# PWR_RELAY.net
KiCad netlist of a schematic drawn in Altium Designer
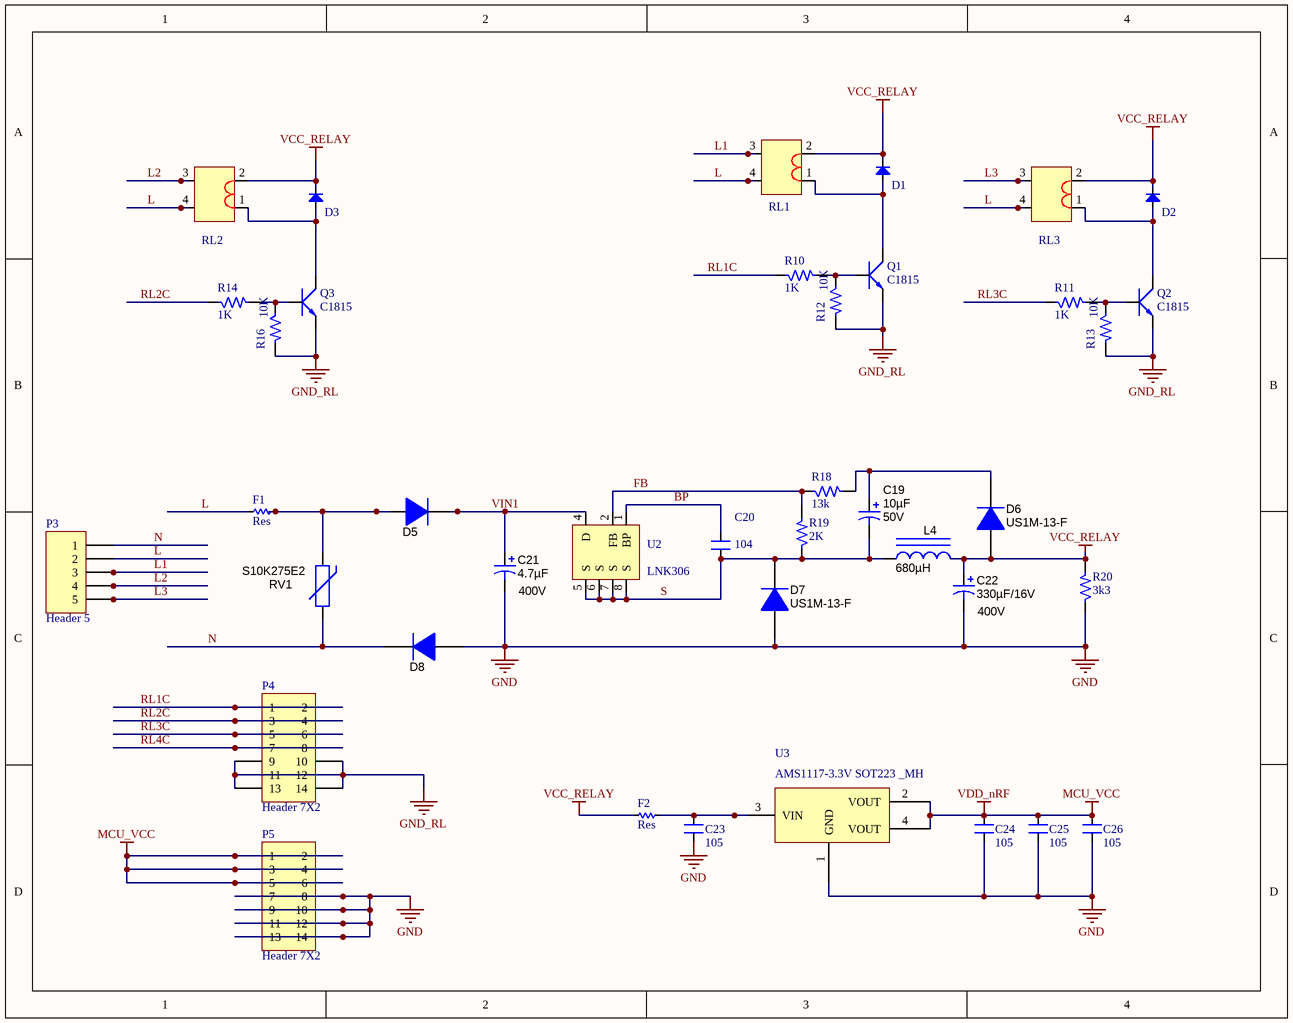
[diagram p0: PWR&RELAY.SchDoc]

(export (version "E")
  (design (tool "Eeschema 10.0.6"))
  (components
    (comp (ref "C19")
      (value "ECA-1HHG100")
      (footprint "PcbLib1:NHG_500x1100")
      (description "CAP, AL, 10 µF, 50 V, +/- 20%, TH")
      (fields
        (field (name "VALUEDISPLAYED") "10µF")
        (field (name "MANUFACTURER") "Panasonic")
        (field (name "VALUE2") "50V")
        (field (name "PUBLISHER") "Texas Instruments")
      )
      (libsource (lib "Capacitor_Aluminum") (part "ECA-1HHG100"))
    )
    (comp (ref "C20")
      (value "104")
      (footprint "0805_HV")
      (description "Cap SMD")
      (libsource (lib "hatcatbietbay") (part "CM"))
    )
    (comp (ref "C21")
      (value "400AX6R8M8x11")
      (footprint "PcbLib1:PANACAP-G-GENERIC")
      (description "CAP, AL, 6.8uF, 400V, +/-20%, TH")
      (fields
        (field (name "VALUEDISPLAYED") "4.7µF")
        (field (name "MANUFACTURER") "Rubycon")
        (field (name "VALUE2") "400V")
        (field (name "PUBLISHER") "Texas Instruments")
      )
      (libsource (lib "Capacitor_Aluminum") (part "400AX6R8M8x11"))
    )
    (comp (ref "C22")
      (value "400AX6R8M8x11")
      (footprint "PcbLib1:CAPPRD350W60D800H1100")
      (description "CAP, AL, 6.8uF, 400V, +/-20%, TH")
      (fields
        (field (name "VALUEDISPLAYED") "330µF/16V")
        (field (name "MANUFACTURER") "Rubycon")
        (field (name "VALUE2") "400V")
        (field (name "PUBLISHER") "Texas Instruments")
      )
      (libsource (lib "Capacitor_Aluminum") (part "400AX6R8M8x11"))
    )
    (comp (ref "C23")
      (value "105")
      (footprint "0805_HV")
      (description "Cap SMD")
      (libsource (lib "hatcatbietbay") (part "CM"))
    )
    (comp (ref "C24")
      (value "105")
      (footprint "0805_HV")
      (description "Cap SMD")
      (libsource (lib "hatcatbietbay") (part "CM"))
    )
    (comp (ref "C25")
      (value "105")
      (footprint "0805_HV")
      (description "Cap SMD")
      (libsource (lib "hatcatbietbay") (part "CM"))
    )
    (comp (ref "C26")
      (value "105")
      (footprint "0805_HV")
      (description "Cap SMD")
      (libsource (lib "hatcatbietbay") (part "CM"))
    )
    (comp (ref "D1")
      (value "Diode SMD")
      (footprint "DIO-SMD-123")
      (description "Default Diode")
      (fields (field (name "PUBLISHER") "Altium Limited"))
      (libsource (lib "LIBRARY") (part "Diode SMD"))
    )
    (comp (ref "D2")
      (value "Diode SMD")
      (footprint "DIO-SMD-123")
      (description "Default Diode")
      (fields (field (name "PUBLISHER") "Altium Limited"))
      (libsource (lib "LIBRARY") (part "Diode SMD"))
    )
    (comp (ref "D3")
      (value "Diode SMD")
      (footprint "DIO-SMD-123")
      (description "Default Diode")
      (fields (field (name "PUBLISHER") "Altium Limited"))
      (libsource (lib "LIBRARY") (part "Diode SMD"))
    )
    (comp (ref "D5")
      (value "US1M-13-F")
      (footprint "PcbLib1:SMB")
      (description "Diode, Ultrafast, 600V, 1A, SMB")
      (fields (field (name "MANUFACTURER") "Diodes Inc.") (field (name "PUBLISHER") "Texas Instruments"))
      (libsource (lib "Diode") (part "MURS160-13-F"))
    )
    (comp (ref "D6")
      (value "US1M-13-F")
      (footprint "PcbLib1:SMB")
      (description "Diode, Ultrafast, 600V, 1A, SMB")
      (fields
        (field (name "PARTNUMBER") "US1M-13-F")
        (field (name "MANUFACTURER") "Diodes Inc.")
        (field (name "PUBLISHER") "Texas Instruments")
      )
      (libsource (lib "Diode") (part "MURS160-13-F"))
    )
    (comp (ref "D7")
      (value "US1M-13-F")
      (footprint "PcbLib1:SMB")
      (description "Diode, Ultrafast, 600V, 1A, SMB")
      (fields
        (field (name "PARTNUMBER") "US1M-13-F")
        (field (name "MANUFACTURER") "Diodes Inc.")
        (field (name "PUBLISHER") "Texas Instruments")
      )
      (libsource (lib "Diode") (part "MURS160-13-F"))
    )
    (comp (ref "D8")
      (value "US1M-13-F")
      (footprint "PcbLib1:SMB")
      (description "Diode, Ultrafast, 600V, 1A, SMB")
      (fields (field (name "MANUFACTURER") "Diodes Inc.") (field (name "PUBLISHER") "Texas Instruments"))
      (libsource (lib "Diode") (part "MURS160-13-F"))
    )
    (comp (ref "F1")
      (value "Res")
      (footprint "1206")
      (description "Resistor")
      (fields
        (field (name "MANUFACTURER") "Generic Components")
        (field (name "PUBLISHER") "Altium Hobart Technology Centre")
      )
      (libsource (lib "LIBRARY") (part "Res-SMD"))
    )
    (comp (ref "F2")
      (value "Res")
      (footprint "1206")
      (description "Resistor")
      (fields
        (field (name "MANUFACTURER") "Generic Components")
        (field (name "PUBLISHER") "Altium Hobart Technology Centre")
      )
      (libsource (lib "LIBRARY") (part "Res-SMD"))
    )
    (comp (ref "L4")
      (value "7447480331")
      (footprint "PcbLib1:IND_WE-TI_8095")
      (description "Inductor, Wirewound, Ferrite, 330 µH, 1.4 A, 0.3 ohm, TH")
      (fields
        (field (name "VALUEDISPLAYED") "680µH")
        (field (name "MANUFACTURER") "Wurth Elektronik")
        (field (name "PUBLISHER") "Texas Instruments")
      )
      (libsource (lib "Inductor_Wurth") (part "7447480331"))
    )
    (comp (ref "P3")
      (value "Header 5")
      (footprint "CONWALL_SWITH-3")
      (description "Header, 5-Pin")
      (fields (field (name "PUBLISHER") "Altium Limited"))
      (libsource (lib "Miscellaneous Connectors") (part "Header 5"))
    )
    (comp (ref "P4")
      (value "Header 7X2")
      (footprint "CON14_1.27")
      (description "Header, 7-Pin, Dual row")
      (fields (field (name "PUBLISHER") "Altium Limited"))
      (libsource (lib "Miscellaneous Connectors") (part "Header 7X2"))
    )
    (comp (ref "P5")
      (value "Header 7X2")
      (footprint "CON14_1.27")
      (description "Header, 7-Pin, Dual row")
      (fields (field (name "PUBLISHER") "Altium Limited"))
      (libsource (lib "Miscellaneous Connectors") (part "Header 7X2"))
    )
    (comp (ref "Q1")
      (value "C1815")
      (footprint "SOT23B")
      (description "NPN 600mW, ECB")
      (libsource (lib "hatcatbietbay") (part "C1815"))
    )
    (comp (ref "Q2")
      (value "C1815")
      (footprint "SOT23B")
      (description "NPN 600mW, ECB")
      (libsource (lib "hatcatbietbay") (part "C1815"))
    )
    (comp (ref "Q3")
      (value "C1815")
      (footprint "SOT23B")
      (description "NPN 600mW, ECB")
      (libsource (lib "hatcatbietbay") (part "C1815"))
    )
    (comp (ref "R10")
      (value "1K")
      (footprint "PcbLib1:0603")
      (description "Resistor 1/4W")
      (libsource (lib "hatcatbietbay") (part "R"))
    )
    (comp (ref "R11")
      (value "1K")
      (footprint "PcbLib1:0603")
      (description "Resistor 1/4W")
      (libsource (lib "hatcatbietbay") (part "R"))
    )
    (comp (ref "R12")
      (value "10K")
      (footprint "PcbLib1:0603")
      (description "Resistor 1/4W")
      (libsource (lib "hatcatbietbay") (part "R"))
    )
    (comp (ref "R13")
      (value "10K")
      (footprint "PcbLib1:0603")
      (description "Resistor 1/4W")
      (libsource (lib "hatcatbietbay") (part "R"))
    )
    (comp (ref "R14")
      (value "1K")
      (footprint "PcbLib1:0603")
      (description "Resistor 1/4W")
      (libsource (lib "hatcatbietbay") (part "R"))
    )
    (comp (ref "R16")
      (value "10K")
      (footprint "PcbLib1:0603")
      (description "Resistor 1/4W")
      (libsource (lib "hatcatbietbay") (part "R"))
    )
    (comp (ref "R18")
      (value "13k")
      (footprint "0805_HV")
      (description "Resistor 1/4W")
      (libsource (lib "hatcatbietbay") (part "R"))
    )
    (comp (ref "R19")
      (value "2K")
      (footprint "0805_HV")
      (description "Resistor 1/4W")
      (libsource (lib "hatcatbietbay") (part "R"))
    )
    (comp (ref "R20")
      (value "3k3")
      (footprint "0805_HV")
      (description "Resistor 1/4W")
      (libsource (lib "hatcatbietbay") (part "R"))
    )
    (comp (ref "RL1")
      (value "Component_1")
      (footprint "AZ7705")
      (libsource (lib "Zettler") (part "Component_1"))
    )
    (comp (ref "RL2")
      (value "Component_1")
      (footprint "AZ7705")
      (libsource (lib "Zettler") (part "Component_1"))
    )
    (comp (ref "RL3")
      (value "Component_1")
      (footprint "AZ7705")
      (libsource (lib "Zettler") (part "Component_1"))
    )
    (comp (ref "RV1")
      (value "S10K275E2")
      (footprint "PcbLib1:VAR_S10K275E2")
      (description "Varistor 275V RMS 10MM Radial, TH")
      (fields
        (field (name "MANUFACTURER") "EPCOS Inc")
        (field (name "SYMBOLCREATOR") "a0412235")
        (field (name "PUBLISHER") "Texas Instruments")
      )
      (libsource (lib "Other_Passive") (part "S10K275E2"))
    )
    (comp (ref "U2") (value "LNK306") (footprint "SOP 7") (libsource (lib "LNK304") (part "Component_1")))
    (comp (ref "U3")
      (value "AMS1117-3.3V SOT223 _MH")
      (footprint "SOT223")
      (libsource (lib "MH_DA_THU_VIEN_16122016") (part "AMS1117-3.3V SOT223 _MH"))
    )
  )
  (nets
    (net (code "1") (name "/BP") (class "Default")
      (node (ref "C20") (pin "2") (pinfunction "2_2") (pintype "passive"))
      (node (ref "U2") (pin "1") (pinfunction "BP_1") (pintype "passive"))
    )
    (net (code "2") (name "/FB") (class "Default")
      (node (ref "R18") (pin "1") (pinfunction "1_1") (pintype "passive"))
      (node (ref "R19") (pin "2") (pinfunction "2_2") (pintype "passive"))
      (node (ref "U2") (pin "2") (pinfunction "FB_2") (pintype "passive"))
    )
    (net (code "3") (name "/L") (class "Default")
      (node (ref "F1") (pin "2") (pinfunction "2_2") (pintype "passive"))
      (node (ref "P3") (pin "2") (pinfunction "2_2") (pintype "passive"))
      (node (ref "RL1") (pin "4") (pintype "passive"))
      (node (ref "RL2") (pin "4") (pintype "passive"))
      (node (ref "RL3") (pin "4") (pintype "passive"))
    )
    (net (code "4") (name "/L1") (class "Default")
      (node (ref "P3") (pin "3") (pinfunction "3_3") (pintype "passive"))
      (node (ref "RL1") (pin "3") (pintype "passive"))
    )
    (net (code "5") (name "/L2") (class "Default")
      (node (ref "P3") (pin "4") (pinfunction "4_4") (pintype "passive"))
      (node (ref "RL2") (pin "3") (pintype "passive"))
    )
    (net (code "6") (name "/L3") (class "Default")
      (node (ref "P3") (pin "5") (pinfunction "5_5") (pintype "passive"))
      (node (ref "RL3") (pin "3") (pintype "passive"))
    )
    (net (code "7") (name "/N") (class "Default")
      (node (ref "D8") (pin "1") (pinfunction "K_1") (pintype "passive"))
      (node (ref "P3") (pin "1") (pinfunction "1_1") (pintype "passive"))
      (node (ref "RV1") (pin "1") (pinfunction "1_1") (pintype "passive"))
    )
    (net (code "8") (name "/RL1C") (class "Default")
      (node (ref "P4") (pin "1") (pinfunction "1_1") (pintype "passive"))
      (node (ref "P4") (pin "2") (pinfunction "2_2") (pintype "passive"))
      (node (ref "R10") (pin "1") (pinfunction "1_1") (pintype "passive"))
    )
    (net (code "9") (name "/RL2C") (class "Default")
      (node (ref "P4") (pin "3") (pinfunction "3_3") (pintype "passive"))
      (node (ref "P4") (pin "4") (pinfunction "4_4") (pintype "passive"))
      (node (ref "R14") (pin "1") (pinfunction "1_1") (pintype "passive"))
    )
    (net (code "10") (name "/RL3C") (class "Default")
      (node (ref "P4") (pin "5") (pinfunction "5_5") (pintype "passive"))
      (node (ref "P4") (pin "6") (pinfunction "6_6") (pintype "passive"))
      (node (ref "R11") (pin "1") (pinfunction "1_1") (pintype "passive"))
    )
    (net (code "11") (name "/RL4C") (class "Default")
      (node (ref "P4") (pin "7") (pinfunction "7_7") (pintype "passive"))
      (node (ref "P4") (pin "8") (pinfunction "8_8") (pintype "passive"))
    )
    (net (code "12") (name "/S") (class "Default")
      (node (ref "C19") (pin "2") (pinfunction "-_2") (pintype "passive"))
      (node (ref "C20") (pin "1") (pinfunction "1_1") (pintype "passive"))
      (node (ref "D7") (pin "1") (pinfunction "K_1") (pintype "passive"))
      (node (ref "L4") (pin "1") (pinfunction "1_1") (pintype "passive"))
      (node (ref "R19") (pin "1") (pinfunction "1_1") (pintype "passive"))
      (node (ref "U2") (pin "5") (pinfunction "S_5") (pintype "passive"))
      (node (ref "U2") (pin "6") (pinfunction "S_6") (pintype "passive"))
      (node (ref "U2") (pin "7") (pinfunction "S_7") (pintype "passive"))
      (node (ref "U2") (pin "8") (pinfunction "S_8") (pintype "passive"))
    )
    (net (code "13") (name "/VIN1") (class "Default")
      (node (ref "C21") (pin "1") (pinfunction "+_1") (pintype "passive"))
      (node (ref "D5") (pin "1") (pinfunction "K_1") (pintype "passive"))
      (node (ref "U2") (pin "4") (pinfunction "D_4") (pintype "passive"))
    )
    (net (code "14") (name "GND") (class "Default")
      (node (ref "C21") (pin "2") (pinfunction "-_2") (pintype "passive"))
      (node (ref "C22") (pin "2") (pinfunction "-_2") (pintype "passive"))
      (node (ref "C23") (pin "1") (pinfunction "1_1") (pintype "passive"))
      (node (ref "C24") (pin "1") (pinfunction "1_1") (pintype "passive"))
      (node (ref "C25") (pin "1") (pinfunction "1_1") (pintype "passive"))
      (node (ref "C26") (pin "1") (pinfunction "1_1") (pintype "passive"))
      (node (ref "D7") (pin "2") (pinfunction "A_2") (pintype "passive"))
      (node (ref "D8") (pin "2") (pinfunction "A_2") (pintype "passive"))
      (node (ref "P5") (pin "10") (pinfunction "10_10") (pintype "passive"))
      (node (ref "P5") (pin "11") (pinfunction "11_11") (pintype "passive"))
      (node (ref "P5") (pin "12") (pinfunction "12_12") (pintype "passive"))
      (node (ref "P5") (pin "13") (pinfunction "13_13") (pintype "passive"))
      (node (ref "P5") (pin "14") (pinfunction "14_14") (pintype "passive"))
      (node (ref "P5") (pin "7") (pinfunction "7_7") (pintype "passive"))
      (node (ref "P5") (pin "8") (pinfunction "8_8") (pintype "passive"))
      (node (ref "P5") (pin "9") (pinfunction "9_9") (pintype "passive"))
      (node (ref "R20") (pin "1") (pinfunction "1_1") (pintype "passive"))
      (node (ref "U3") (pin "1") (pinfunction "GND_1") (pintype "passive"))
    )
    (net (code "15") (name "GND_RL") (class "Default")
      (node (ref "P4") (pin "10") (pinfunction "10_10") (pintype "passive"))
      (node (ref "P4") (pin "11") (pinfunction "11_11") (pintype "passive"))
      (node (ref "P4") (pin "12") (pinfunction "12_12") (pintype "passive"))
      (node (ref "P4") (pin "13") (pinfunction "13_13") (pintype "passive"))
      (node (ref "P4") (pin "14") (pinfunction "14_14") (pintype "passive"))
      (node (ref "P4") (pin "9") (pinfunction "9_9") (pintype "passive"))
      (node (ref "Q1") (pin "3") (pinfunction "E_3") (pintype "passive"))
      (node (ref "Q2") (pin "3") (pinfunction "E_3") (pintype "passive"))
      (node (ref "Q3") (pin "3") (pinfunction "E_3") (pintype "passive"))
      (node (ref "R12") (pin "2") (pinfunction "2_2") (pintype "passive"))
      (node (ref "R13") (pin "2") (pinfunction "2_2") (pintype "passive"))
      (node (ref "R16") (pin "2") (pinfunction "2_2") (pintype "passive"))
    )
    (net (code "16") (name "MCU_VCC") (class "Default")
      (node (ref "C24") (pin "2") (pinfunction "2_2") (pintype "passive"))
      (node (ref "C25") (pin "2") (pinfunction "2_2") (pintype "passive"))
      (node (ref "C26") (pin "2") (pinfunction "2_2") (pintype "passive"))
      (node (ref "P5") (pin "1") (pinfunction "1_1") (pintype "passive"))
      (node (ref "P5") (pin "2") (pinfunction "2_2") (pintype "passive"))
      (node (ref "P5") (pin "3") (pinfunction "3_3") (pintype "passive"))
      (node (ref "P5") (pin "4") (pinfunction "4_4") (pintype "passive"))
      (node (ref "P5") (pin "5") (pinfunction "5_5") (pintype "passive"))
      (node (ref "P5") (pin "6") (pinfunction "6_6") (pintype "passive"))
      (node (ref "U3") (pin "2") (pinfunction "VOUT_2") (pintype "passive"))
      (node (ref "U3") (pin "4") (pinfunction "VOUT_4") (pintype "passive"))
    )
    (net (code "17") (name "Net-(C19-+)") (class "Default")
      (node (ref "C19") (pin "1") (pinfunction "+_1") (pintype "passive"))
      (node (ref "D6") (pin "1") (pinfunction "K_1") (pintype "passive"))
      (node (ref "R18") (pin "2") (pinfunction "2_2") (pintype "passive"))
    )
    (net (code "18") (name "Net-(D1-A)") (class "Default")
      (node (ref "D1") (pin "1") (pinfunction "A_1") (pintype "passive"))
      (node (ref "Q1") (pin "2") (pinfunction "C_2") (pintype "passive"))
      (node (ref "RL1") (pin "1") (pintype "passive"))
    )
    (net (code "19") (name "Net-(D2-A)") (class "Default")
      (node (ref "D2") (pin "1") (pinfunction "A_1") (pintype "passive"))
      (node (ref "Q2") (pin "2") (pinfunction "C_2") (pintype "passive"))
      (node (ref "RL3") (pin "1") (pintype "passive"))
    )
    (net (code "20") (name "Net-(D3-A)") (class "Default")
      (node (ref "D3") (pin "1") (pinfunction "A_1") (pintype "passive"))
      (node (ref "Q3") (pin "2") (pinfunction "C_2") (pintype "passive"))
      (node (ref "RL2") (pin "1") (pintype "passive"))
    )
    (net (code "21") (name "Net-(D5-A)") (class "Default")
      (node (ref "D5") (pin "2") (pinfunction "A_2") (pintype "passive"))
      (node (ref "F1") (pin "1") (pinfunction "1_1") (pintype "passive"))
      (node (ref "RV1") (pin "2") (pinfunction "2_2") (pintype "passive"))
    )
    (net (code "22") (name "Net-(Q1-B)") (class "Default")
      (node (ref "Q1") (pin "1") (pinfunction "B_1") (pintype "passive"))
      (node (ref "R10") (pin "2") (pinfunction "2_2") (pintype "passive"))
      (node (ref "R12") (pin "1") (pinfunction "1_1") (pintype "passive"))
    )
    (net (code "23") (name "Net-(Q2-B)") (class "Default")
      (node (ref "Q2") (pin "1") (pinfunction "B_1") (pintype "passive"))
      (node (ref "R11") (pin "2") (pinfunction "2_2") (pintype "passive"))
      (node (ref "R13") (pin "1") (pinfunction "1_1") (pintype "passive"))
    )
    (net (code "24") (name "Net-(Q3-B)") (class "Default")
      (node (ref "Q3") (pin "1") (pinfunction "B_1") (pintype "passive"))
      (node (ref "R14") (pin "2") (pinfunction "2_2") (pintype "passive"))
      (node (ref "R16") (pin "1") (pinfunction "1_1") (pintype "passive"))
    )
    (net (code "25") (name "Net-(U3-VIN)") (class "Default")
      (node (ref "C23") (pin "2") (pinfunction "2_2") (pintype "passive"))
      (node (ref "F2") (pin "1") (pinfunction "1_1") (pintype "passive"))
      (node (ref "U3") (pin "3") (pinfunction "VIN_3") (pintype "passive"))
    )
    (net (code "26") (name "VCC_RELAY") (class "Default")
      (node (ref "C22") (pin "1") (pinfunction "+_1") (pintype "passive"))
      (node (ref "D1") (pin "2") (pinfunction "K_2") (pintype "passive"))
      (node (ref "D2") (pin "2") (pinfunction "K_2") (pintype "passive"))
      (node (ref "D3") (pin "2") (pinfunction "K_2") (pintype "passive"))
      (node (ref "D6") (pin "2") (pinfunction "A_2") (pintype "passive"))
      (node (ref "F2") (pin "2") (pinfunction "2_2") (pintype "passive"))
      (node (ref "L4") (pin "2") (pinfunction "2_2") (pintype "passive"))
      (node (ref "R20") (pin "2") (pinfunction "2_2") (pintype "passive"))
      (node (ref "RL1") (pin "2") (pintype "passive"))
      (node (ref "RL2") (pin "2") (pintype "passive"))
      (node (ref "RL3") (pin "2") (pintype "passive"))
    )
  )
)
